# STMCamera21.net
KiCad netlist of a schematic drawn in Altium Designer
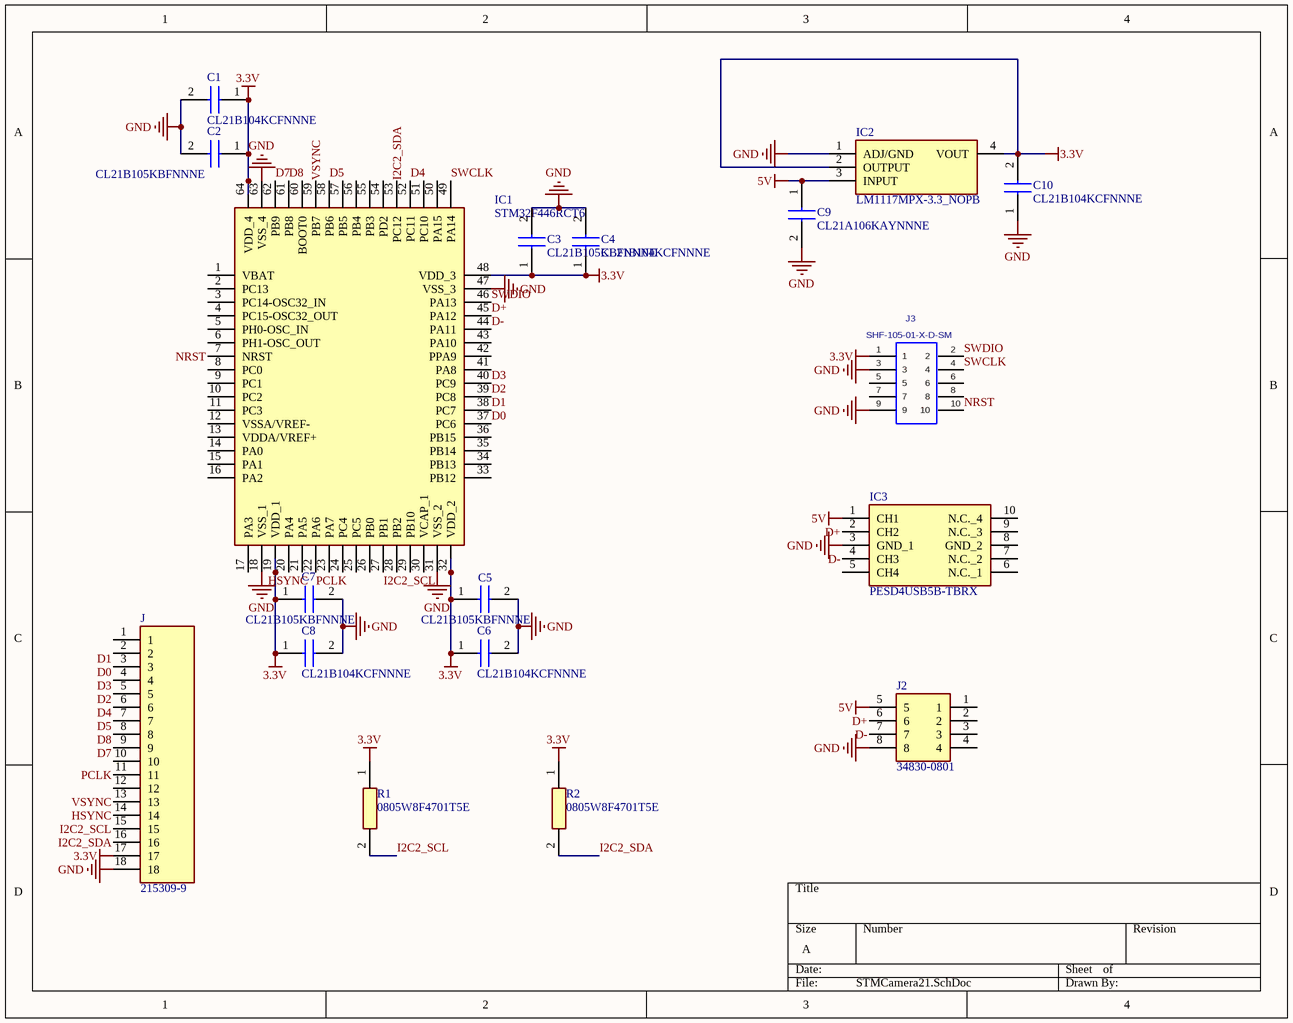
[diagram p0: STMCamera21.SchDoc]

(export (version "E")
  (design (tool "Eeschema 10.0.6"))
  (components
    (comp (ref "C1")
      (value "CL21B104KCFNNNE")
      (footprint "SamacSys:CAPC2012X135N")
      (description "100uF")
      (fields (field (name "MOUSER PART NUMBER") "187-CL21B104KCFNNNE"))
      (libsource (lib "*") (part "CL21B104KCFNNNE"))
    )
    (comp (ref "C2")
      (value "CL21B105KBFNNNE")
      (footprint "SamacSys:CAPC2012X135N")
      (description "1uF")
      (fields (field (name "MOUSER PART NUMBER") "187-CL21B105KBFNNNE"))
      (libsource (lib "*") (part "CL21B105KBFNNNE"))
    )
    (comp (ref "C3")
      (value "CL21B105KBFNNNE")
      (footprint "SamacSys:CAPC2012X135N")
      (description "1uF")
      (fields (field (name "MOUSER PART NUMBER") "187-CL21B105KBFNNNE"))
      (libsource (lib "*") (part "CL21B105KBFNNNE"))
    )
    (comp (ref "C4")
      (value "CL21B104KCFNNNE")
      (footprint "SamacSys:CAPC2012X135N")
      (description "100uF")
      (fields (field (name "MOUSER PART NUMBER") "187-CL21B104KCFNNNE"))
      (libsource (lib "*") (part "CL21B104KCFNNNE"))
    )
    (comp (ref "C5")
      (value "CL21B105KBFNNNE")
      (footprint "SamacSys:CAPC2012X135N")
      (description "1uF")
      (fields (field (name "MOUSER PART NUMBER") "187-CL21B105KBFNNNE"))
      (libsource (lib "*") (part "CL21B105KBFNNNE"))
    )
    (comp (ref "C6")
      (value "CL21B104KCFNNNE")
      (footprint "SamacSys:CAPC2012X135N")
      (description "100uF")
      (fields (field (name "MOUSER PART NUMBER") "187-CL21B104KCFNNNE"))
      (libsource (lib "*") (part "CL21B104KCFNNNE"))
    )
    (comp (ref "C7")
      (value "CL21B105KBFNNNE")
      (footprint "SamacSys:CAPC2012X135N")
      (description "1uF")
      (fields (field (name "MOUSER PART NUMBER") "187-CL21B105KBFNNNE"))
      (libsource (lib "*") (part "CL21B105KBFNNNE"))
    )
    (comp (ref "C8")
      (value "CL21B104KCFNNNE")
      (footprint "SamacSys:CAPC2012X135N")
      (description "100uF")
      (fields (field (name "MOUSER PART NUMBER") "187-CL21B104KCFNNNE"))
      (libsource (lib "*") (part "CL21B104KCFNNNE"))
    )
    (comp (ref "C9")
      (value "CL21A106KAYNNNE")
      (footprint "SamacSys:CAPC2012X145N")
      (description "10uF")
      (fields (field (name "MOUSER PART NUMBER") "187-CL21A106KAYNNNE"))
      (libsource (lib "SamacSys") (part "CL21A106KAYNNNE"))
    )
    (comp (ref "C10")
      (value "CL21B104KCFNNNE")
      (footprint "SamacSys:CAPC2012X135N")
      (description "100uF")
      (fields (field (name "MOUSER PART NUMBER") "187-CL21B104KCFNNNE"))
      (libsource (lib "*") (part "CL21B104KCFNNNE"))
    )
    (comp (ref "IC1")
      (value "STM32F446RCT6")
      (footprint "SamacSys:QFP50P1200X1200X160-64N")
      (description "Integrated Circuit")
      (fields (field (name "MOUSER PART NUMBER") "511-STM32F446RCT6"))
      (libsource (lib "*") (part "STM32F446RCT6"))
    )
    (comp (ref "IC2")
      (value "LM1117MPX-3.3_NOPB")
      (footprint "SamacSys:SOT230P700X180-4N")
      (description "Integrated Circuit")
      (fields
        (field (name "MANUFACTURER_PART_NUMBER") "LM1117MPX-3.3/NOPB")
        (field (name "MOUSER PART NUMBER") "926-LM1117MPX3.3NOPB")
      )
      (libsource (lib "*") (part "LM1117MPX-3.3_NOPB"))
    )
    (comp (ref "IC3")
      (value "PESD4USB5B-TBRX")
      (footprint "SamacSys:PESD4USB5BTBRX")
      (description "Integrated Circuit")
      (fields (field (name "MOUSER PART NUMBER") "771-PESD4USB5B-TBRX"))
      (libsource (lib "*") (part "PESD4USB5B-TBRX"))
    )
    (comp (ref "J")
      (value "215309-9")
      (footprint "SnapEDApcb:TE_215309-9")
      (description "2X9P HV100 REC CON. TE, 8.5MM")
      (fields (field (name "MF") "TE Connectivity"))
      (libsource (lib "SnapEDAsch") (part "215309-9"))
    )
    (comp (ref "J2")
      (value "34830-0801")
      (footprint "SamacSys:348300801")
      (description "Connector")
      (fields (field (name "MOUSER PART NUMBER") "538-34830-0801"))
      (libsource (lib "*") (part "34830-0801"))
    )
    (comp (ref "J3")
      (value "SHF-105-01-X-D-SM")
      (footprint "SHF-105-01-X-D-SM")
      (description "0.05\"X0.05\" SHROUDED TERMINAL STRIP, 10 PINS.")
      (fields (field (name "MANUFACTURER") "SAMTEC") (field (name "CREATED") "February 17, 2015 - Wendy Xin"))
      (libsource (lib "SHF-105-01-X-D-SM") (part "SHF-105-01-X-D-SM"))
    )
    (comp (ref "R1")
      (value "0805W8F4701T5E")
      (footprint "SamacSys:TNPV0805180KBEEA")
      (description "4.7k")
      (fields
        (field (name "MANUFACTURER_PART_NUMBER") "TNPV0805180KBEEA")
        (field (name "MOUSER PART NUMBER") "71-TNPV0805180KBEEA")
      )
      (libsource (lib "SamacSys") (part "TNPV0805180KBEEA"))
    )
    (comp (ref "R2")
      (value "0805W8F4701T5E")
      (footprint "SamacSys:TNPV0805180KBEEA")
      (description "4.7k")
      (fields
        (field (name "MANUFACTURER_PART_NUMBER") "TNPV0805180KBEEA")
        (field (name "MOUSER PART NUMBER") "71-TNPV0805180KBEEA")
      )
      (libsource (lib "SamacSys") (part "TNPV0805180KBEEA"))
    )
  )
  (nets
    (net (code "1") (name "/D+") (class "Default")
      (node (ref "IC1") (pin "45") (pinfunction "PA12_45") (pintype "passive"))
      (node (ref "IC3") (pin "2") (pinfunction "CH2_2") (pintype "passive"))
      (node (ref "J2") (pin "6") (pinfunction "6_6") (pintype "passive"))
    )
    (net (code "2") (name "/D-") (class "Default")
      (node (ref "IC1") (pin "44") (pinfunction "PA11_44") (pintype "passive"))
      (node (ref "IC3") (pin "4") (pinfunction "CH3_4") (pintype "passive"))
      (node (ref "J2") (pin "7") (pinfunction "7_7") (pintype "passive"))
    )
    (net (code "3") (name "/D0") (class "Default")
      (node (ref "IC1") (pin "37") (pinfunction "PC6_37") (pintype "passive"))
      (node (ref "J") (pin "4") (pinfunction "4_4") (pintype "passive"))
    )
    (net (code "4") (name "/D1") (class "Default")
      (node (ref "IC1") (pin "38") (pinfunction "PC7_38") (pintype "passive"))
      (node (ref "J") (pin "3") (pinfunction "3_3") (pintype "passive"))
    )
    (net (code "5") (name "/D2") (class "Default")
      (node (ref "IC1") (pin "39") (pinfunction "PC8_39") (pintype "passive"))
      (node (ref "J") (pin "6") (pinfunction "6_6") (pintype "passive"))
    )
    (net (code "6") (name "/D3") (class "Default")
      (node (ref "IC1") (pin "40") (pinfunction "PC9_40") (pintype "passive"))
      (node (ref "J") (pin "5") (pinfunction "5_5") (pintype "passive"))
    )
    (net (code "7") (name "/D4") (class "Default")
      (node (ref "IC1") (pin "52") (pinfunction "PC11_52") (pintype "passive"))
      (node (ref "J") (pin "7") (pinfunction "7_7") (pintype "passive"))
    )
    (net (code "8") (name "/D5") (class "Default")
      (node (ref "IC1") (pin "58") (pinfunction "PB6_58") (pintype "passive"))
      (node (ref "J") (pin "8") (pinfunction "8_8") (pintype "passive"))
    )
    (net (code "9") (name "/D7") (class "Default")
      (node (ref "IC1") (pin "62") (pinfunction "PB9_62") (pintype "passive"))
      (node (ref "J") (pin "10") (pinfunction "10_10") (pintype "passive"))
    )
    (net (code "10") (name "/D8") (class "Default")
      (node (ref "IC1") (pin "61") (pinfunction "PB8_61") (pintype "passive"))
      (node (ref "J") (pin "9") (pinfunction "9_9") (pintype "passive"))
    )
    (net (code "11") (name "/HSYNC") (class "Default")
      (node (ref "IC1") (pin "20") (pinfunction "PA4_20") (pintype "passive"))
      (node (ref "J") (pin "14") (pinfunction "14_14") (pintype "passive"))
    )
    (net (code "12") (name "/I2C2_SCL") (class "Default")
      (node (ref "IC1") (pin "29") (pinfunction "PB10_29") (pintype "passive"))
      (node (ref "J") (pin "15") (pinfunction "15_15") (pintype "passive"))
      (node (ref "R1") (pin "2") (pinfunction "2_2") (pintype "passive"))
    )
    (net (code "13") (name "/I2C2_SDA") (class "Default")
      (node (ref "IC1") (pin "53") (pinfunction "PC12_53") (pintype "passive"))
      (node (ref "J") (pin "16") (pinfunction "16_16") (pintype "passive"))
      (node (ref "R2") (pin "2") (pinfunction "2_2") (pintype "passive"))
    )
    (net (code "14") (name "/NRST") (class "Default")
      (node (ref "IC1") (pin "7") (pinfunction "NRST_7") (pintype "passive"))
      (node (ref "J3") (pin "10") (pinfunction "10_10") (pintype "passive"))
    )
    (net (code "15") (name "/PCLK") (class "Default")
      (node (ref "IC1") (pin "22") (pinfunction "PA6_22") (pintype "passive"))
      (node (ref "J") (pin "11") (pinfunction "11_11") (pintype "passive"))
    )
    (net (code "16") (name "/SWCLK") (class "Default")
      (node (ref "IC1") (pin "49") (pinfunction "PA14_49") (pintype "passive"))
      (node (ref "J3") (pin "4") (pinfunction "4_4") (pintype "passive"))
    )
    (net (code "17") (name "/SWDIO") (class "Default")
      (node (ref "IC1") (pin "46") (pinfunction "PA13_46") (pintype "passive"))
      (node (ref "J3") (pin "2") (pinfunction "2_2") (pintype "passive"))
    )
    (net (code "18") (name "/VSYNC") (class "Default")
      (node (ref "IC1") (pin "59") (pinfunction "PB7_59") (pintype "passive"))
      (node (ref "J") (pin "13") (pinfunction "13_13") (pintype "passive"))
    )
    (net (code "19") (name "3.3V") (class "Default")
      (node (ref "C1") (pin "1") (pinfunction "1_1") (pintype "passive"))
      (node (ref "C10") (pin "2") (pinfunction "2_2") (pintype "passive"))
      (node (ref "C2") (pin "1") (pinfunction "1_1") (pintype "passive"))
      (node (ref "C3") (pin "1") (pinfunction "1_1") (pintype "passive"))
      (node (ref "C4") (pin "1") (pinfunction "1_1") (pintype "passive"))
      (node (ref "C5") (pin "1") (pinfunction "1_1") (pintype "passive"))
      (node (ref "C6") (pin "1") (pinfunction "1_1") (pintype "passive"))
      (node (ref "C7") (pin "1") (pinfunction "1_1") (pintype "passive"))
      (node (ref "C8") (pin "1") (pinfunction "1_1") (pintype "passive"))
      (node (ref "IC1") (pin "19") (pinfunction "VDD_1_19") (pintype "passive"))
      (node (ref "IC1") (pin "32") (pinfunction "VDD_2_32") (pintype "passive"))
      (node (ref "IC1") (pin "48") (pinfunction "VDD_3_48") (pintype "passive"))
      (node (ref "IC1") (pin "64") (pinfunction "VDD_4_64") (pintype "passive"))
      (node (ref "IC2") (pin "2") (pinfunction "OUTPUT_2") (pintype "passive"))
      (node (ref "IC2") (pin "4") (pinfunction "VOUT_4") (pintype "passive"))
      (node (ref "J") (pin "17") (pinfunction "17_17") (pintype "passive"))
      (node (ref "J3") (pin "1") (pinfunction "1_1") (pintype "passive"))
      (node (ref "R1") (pin "1") (pinfunction "1_1") (pintype "passive"))
      (node (ref "R2") (pin "1") (pinfunction "1_1") (pintype "passive"))
    )
    (net (code "20") (name "5V") (class "Default")
      (node (ref "C9") (pin "1") (pinfunction "1_1") (pintype "passive"))
      (node (ref "IC2") (pin "3") (pinfunction "INPUT_3") (pintype "passive"))
      (node (ref "IC3") (pin "1") (pinfunction "CH1_1") (pintype "passive"))
      (node (ref "J2") (pin "5") (pinfunction "5_5") (pintype "passive"))
    )
    (net (code "21") (name "GND") (class "Default")
      (node (ref "C1") (pin "2") (pinfunction "2_2") (pintype "passive"))
      (node (ref "C10") (pin "1") (pinfunction "1_1") (pintype "passive"))
      (node (ref "C2") (pin "2") (pinfunction "2_2") (pintype "passive"))
      (node (ref "C3") (pin "2") (pinfunction "2_2") (pintype "passive"))
      (node (ref "C4") (pin "2") (pinfunction "2_2") (pintype "passive"))
      (node (ref "C5") (pin "2") (pinfunction "2_2") (pintype "passive"))
      (node (ref "C6") (pin "2") (pinfunction "2_2") (pintype "passive"))
      (node (ref "C7") (pin "2") (pinfunction "2_2") (pintype "passive"))
      (node (ref "C8") (pin "2") (pinfunction "2_2") (pintype "passive"))
      (node (ref "C9") (pin "2") (pinfunction "2_2") (pintype "passive"))
      (node (ref "IC1") (pin "18") (pinfunction "VSS_1_18") (pintype "passive"))
      (node (ref "IC1") (pin "31") (pinfunction "VSS_2_31") (pintype "passive"))
      (node (ref "IC1") (pin "47") (pinfunction "VSS_3_47") (pintype "passive"))
      (node (ref "IC1") (pin "63") (pinfunction "VSS_4_63") (pintype "passive"))
      (node (ref "IC2") (pin "1") (pinfunction "ADJ/GND_1") (pintype "passive"))
      (node (ref "IC3") (pin "3") (pinfunction "GND_1_3") (pintype "passive"))
      (node (ref "J") (pin "18") (pinfunction "18_18") (pintype "passive"))
      (node (ref "J2") (pin "8") (pinfunction "8_8") (pintype "passive"))
      (node (ref "J3") (pin "3") (pinfunction "3_3") (pintype "passive"))
      (node (ref "J3") (pin "9") (pinfunction "9_9") (pintype "passive"))
    )
    (net (code "22") (name "unconnected-(IC1-BOOT0-Pad60)") (class "Default")
      (node (ref "IC1") (pin "60") (pinfunction "BOOT0_60") (pintype "passive"))
    )
    (net (code "23") (name "unconnected-(IC1-PA0-Pad14)") (class "Default")
      (node (ref "IC1") (pin "14") (pinfunction "PA0_14") (pintype "passive"))
    )
    (net (code "24") (name "unconnected-(IC1-PA1-Pad15)") (class "Default")
      (node (ref "IC1") (pin "15") (pinfunction "PA1_15") (pintype "passive"))
    )
    (net (code "25") (name "unconnected-(IC1-PA2-Pad16)") (class "Default")
      (node (ref "IC1") (pin "16") (pinfunction "PA2_16") (pintype "passive"))
    )
    (net (code "26") (name "unconnected-(IC1-PA3-Pad17)") (class "Default")
      (node (ref "IC1") (pin "17") (pinfunction "PA3_17") (pintype "passive"))
    )
    (net (code "27") (name "unconnected-(IC1-PA5-Pad21)") (class "Default")
      (node (ref "IC1") (pin "21") (pinfunction "PA5_21") (pintype "passive"))
    )
    (net (code "28") (name "unconnected-(IC1-PA7-Pad23)") (class "Default")
      (node (ref "IC1") (pin "23") (pinfunction "PA7_23") (pintype "passive"))
    )
    (net (code "29") (name "unconnected-(IC1-PA8-Pad41)") (class "Default")
      (node (ref "IC1") (pin "41") (pinfunction "PA8_41") (pintype "passive"))
    )
    (net (code "30") (name "unconnected-(IC1-PA10-Pad43)") (class "Default")
      (node (ref "IC1") (pin "43") (pinfunction "PA10_43") (pintype "passive"))
    )
    (net (code "31") (name "unconnected-(IC1-PA15-Pad50)") (class "Default")
      (node (ref "IC1") (pin "50") (pinfunction "PA15_50") (pintype "passive"))
    )
    (net (code "32") (name "unconnected-(IC1-PB0-Pad26)") (class "Default")
      (node (ref "IC1") (pin "26") (pinfunction "PB0_26") (pintype "passive"))
    )
    (net (code "33") (name "unconnected-(IC1-PB1-Pad27)") (class "Default")
      (node (ref "IC1") (pin "27") (pinfunction "PB1_27") (pintype "passive"))
    )
    (net (code "34") (name "unconnected-(IC1-PB2-Pad28)") (class "Default")
      (node (ref "IC1") (pin "28") (pinfunction "PB2_28") (pintype "passive"))
    )
    (net (code "35") (name "unconnected-(IC1-PB3-Pad55)") (class "Default")
      (node (ref "IC1") (pin "55") (pinfunction "PB3_55") (pintype "passive"))
    )
    (net (code "36") (name "unconnected-(IC1-PB4-Pad56)") (class "Default")
      (node (ref "IC1") (pin "56") (pinfunction "PB4_56") (pintype "passive"))
    )
    (net (code "37") (name "unconnected-(IC1-PB5-Pad57)") (class "Default")
      (node (ref "IC1") (pin "57") (pinfunction "PB5_57") (pintype "passive"))
    )
    (net (code "38") (name "unconnected-(IC1-PB12-Pad33)") (class "Default")
      (node (ref "IC1") (pin "33") (pinfunction "PB12_33") (pintype "passive"))
    )
    (net (code "39") (name "unconnected-(IC1-PB13-Pad34)") (class "Default")
      (node (ref "IC1") (pin "34") (pinfunction "PB13_34") (pintype "passive"))
    )
    (net (code "40") (name "unconnected-(IC1-PB14-Pad35)") (class "Default")
      (node (ref "IC1") (pin "35") (pinfunction "PB14_35") (pintype "passive"))
    )
    (net (code "41") (name "unconnected-(IC1-PB15-Pad36)") (class "Default")
      (node (ref "IC1") (pin "36") (pinfunction "PB15_36") (pintype "passive"))
    )
    (net (code "42") (name "unconnected-(IC1-PC0-Pad8)") (class "Default")
      (node (ref "IC1") (pin "8") (pinfunction "PC0_8") (pintype "passive"))
    )
    (net (code "43") (name "unconnected-(IC1-PC1-Pad9)") (class "Default")
      (node (ref "IC1") (pin "9") (pinfunction "PC1_9") (pintype "passive"))
    )
    (net (code "44") (name "unconnected-(IC1-PC2-Pad10)") (class "Default")
      (node (ref "IC1") (pin "10") (pinfunction "PC2_10") (pintype "passive"))
    )
    (net (code "45") (name "unconnected-(IC1-PC3-Pad11)") (class "Default")
      (node (ref "IC1") (pin "11") (pinfunction "PC3_11") (pintype "passive"))
    )
    (net (code "46") (name "unconnected-(IC1-PC4-Pad24)") (class "Default")
      (node (ref "IC1") (pin "24") (pinfunction "PC4_24") (pintype "passive"))
    )
    (net (code "47") (name "unconnected-(IC1-PC5-Pad25)") (class "Default")
      (node (ref "IC1") (pin "25") (pinfunction "PC5_25") (pintype "passive"))
    )
    (net (code "48") (name "unconnected-(IC1-PC10-Pad51)") (class "Default")
      (node (ref "IC1") (pin "51") (pinfunction "PC10_51") (pintype "passive"))
    )
    (net (code "49") (name "unconnected-(IC1-PC13-Pad2)") (class "Default")
      (node (ref "IC1") (pin "2") (pinfunction "PC13_2") (pintype "passive"))
    )
    (net (code "50") (name "unconnected-(IC1-PC14-OSC32_IN-Pad3)") (class "Default")
      (node (ref "IC1") (pin "3") (pinfunction "PC14-OSC32_IN_3") (pintype "passive"))
    )
    (net (code "51") (name "unconnected-(IC1-PC15-OSC32_OUT-Pad4)") (class "Default")
      (node (ref "IC1") (pin "4") (pinfunction "PC15-OSC32_OUT_4") (pintype "passive"))
    )
    (net (code "52") (name "unconnected-(IC1-PD2-Pad54)") (class "Default")
      (node (ref "IC1") (pin "54") (pinfunction "PD2_54") (pintype "passive"))
    )
    (net (code "53") (name "unconnected-(IC1-PH0-OSC_IN-Pad5)") (class "Default")
      (node (ref "IC1") (pin "5") (pinfunction "PH0-OSC_IN_5") (pintype "passive"))
    )
    (net (code "54") (name "unconnected-(IC1-PH1-OSC_OUT-Pad6)") (class "Default")
      (node (ref "IC1") (pin "6") (pinfunction "PH1-OSC_OUT_6") (pintype "passive"))
    )
    (net (code "55") (name "unconnected-(IC1-PPA9-Pad42)") (class "Default")
      (node (ref "IC1") (pin "42") (pinfunction "PPA9_42") (pintype "passive"))
    )
    (net (code "56") (name "unconnected-(IC1-VBAT-Pad1)") (class "Default")
      (node (ref "IC1") (pin "1") (pinfunction "VBAT_1") (pintype "passive"))
    )
    (net (code "57") (name "unconnected-(IC1-VCAP_1-Pad30)") (class "Default")
      (node (ref "IC1") (pin "30") (pinfunction "VCAP_1_30") (pintype "passive"))
    )
    (net (code "58") (name "unconnected-(IC1-VDDA{slash}VREF+-Pad13)") (class "Default")
      (node (ref "IC1") (pin "13") (pinfunction "VDDA/VREF+_13") (pintype "passive"))
    )
    (net (code "59") (name "unconnected-(IC1-VSSA{slash}VREF--Pad12)") (class "Default")
      (node (ref "IC1") (pin "12") (pinfunction "VSSA/VREF-_12") (pintype "passive"))
    )
    (net (code "60") (name "unconnected-(IC3-CH4-Pad5)") (class "Default")
      (node (ref "IC3") (pin "5") (pinfunction "CH4_5") (pintype "passive"))
    )
    (net (code "61") (name "unconnected-(IC3-GND_2-Pad8)") (class "Default")
      (node (ref "IC3") (pin "8") (pinfunction "GND_2_8") (pintype "passive"))
    )
    (net (code "62") (name "unconnected-(IC3-N.C._1-Pad6)") (class "Default")
      (node (ref "IC3") (pin "6") (pinfunction "N.C._1_6") (pintype "passive"))
    )
    (net (code "63") (name "unconnected-(IC3-N.C._2-Pad7)") (class "Default")
      (node (ref "IC3") (pin "7") (pinfunction "N.C._2_7") (pintype "passive"))
    )
    (net (code "64") (name "unconnected-(IC3-N.C._3-Pad9)") (class "Default")
      (node (ref "IC3") (pin "9") (pinfunction "N.C._3_9") (pintype "passive"))
    )
    (net (code "65") (name "unconnected-(IC3-N.C._4-Pad10)") (class "Default")
      (node (ref "IC3") (pin "10") (pinfunction "N.C._4_10") (pintype "passive"))
    )
    (net (code "66") (name "unconnected-(J-Pad1)") (class "Default")
      (node (ref "J") (pin "1") (pinfunction "1_1") (pintype "passive"))
    )
    (net (code "67") (name "unconnected-(J-Pad2)") (class "Default")
      (node (ref "J") (pin "2") (pinfunction "2_2") (pintype "passive"))
    )
    (net (code "68") (name "unconnected-(J-Pad12)") (class "Default")
      (node (ref "J") (pin "12") (pinfunction "12_12") (pintype "passive"))
    )
    (net (code "69") (name "unconnected-(J2-Pad1)") (class "Default")
      (node (ref "J2") (pin "1") (pinfunction "1_1") (pintype "passive"))
    )
    (net (code "70") (name "unconnected-(J2-Pad2)") (class "Default")
      (node (ref "J2") (pin "2") (pinfunction "2_2") (pintype "passive"))
    )
    (net (code "71") (name "unconnected-(J2-Pad3)") (class "Default")
      (node (ref "J2") (pin "3") (pinfunction "3_3") (pintype "passive"))
    )
    (net (code "72") (name "unconnected-(J2-Pad4)") (class "Default")
      (node (ref "J2") (pin "4") (pinfunction "4_4") (pintype "passive"))
    )
    (net (code "73") (name "unconnected-(J3-Pad5)") (class "Default")
      (node (ref "J3") (pin "5") (pinfunction "5_5") (pintype "passive"))
    )
    (net (code "74") (name "unconnected-(J3-Pad6)") (class "Default")
      (node (ref "J3") (pin "6") (pinfunction "6_6") (pintype "passive"))
    )
    (net (code "75") (name "unconnected-(J3-Pad7)") (class "Default")
      (node (ref "J3") (pin "7") (pinfunction "7_7") (pintype "passive"))
    )
    (net (code "76") (name "unconnected-(J3-Pad8)") (class "Default")
      (node (ref "J3") (pin "8") (pinfunction "8_8") (pintype "passive"))
    )
  )
)
